# LPCB220_-_AUXPROP_INTERFACE.net
KiCad netlist of a schematic drawn in Altium Designer
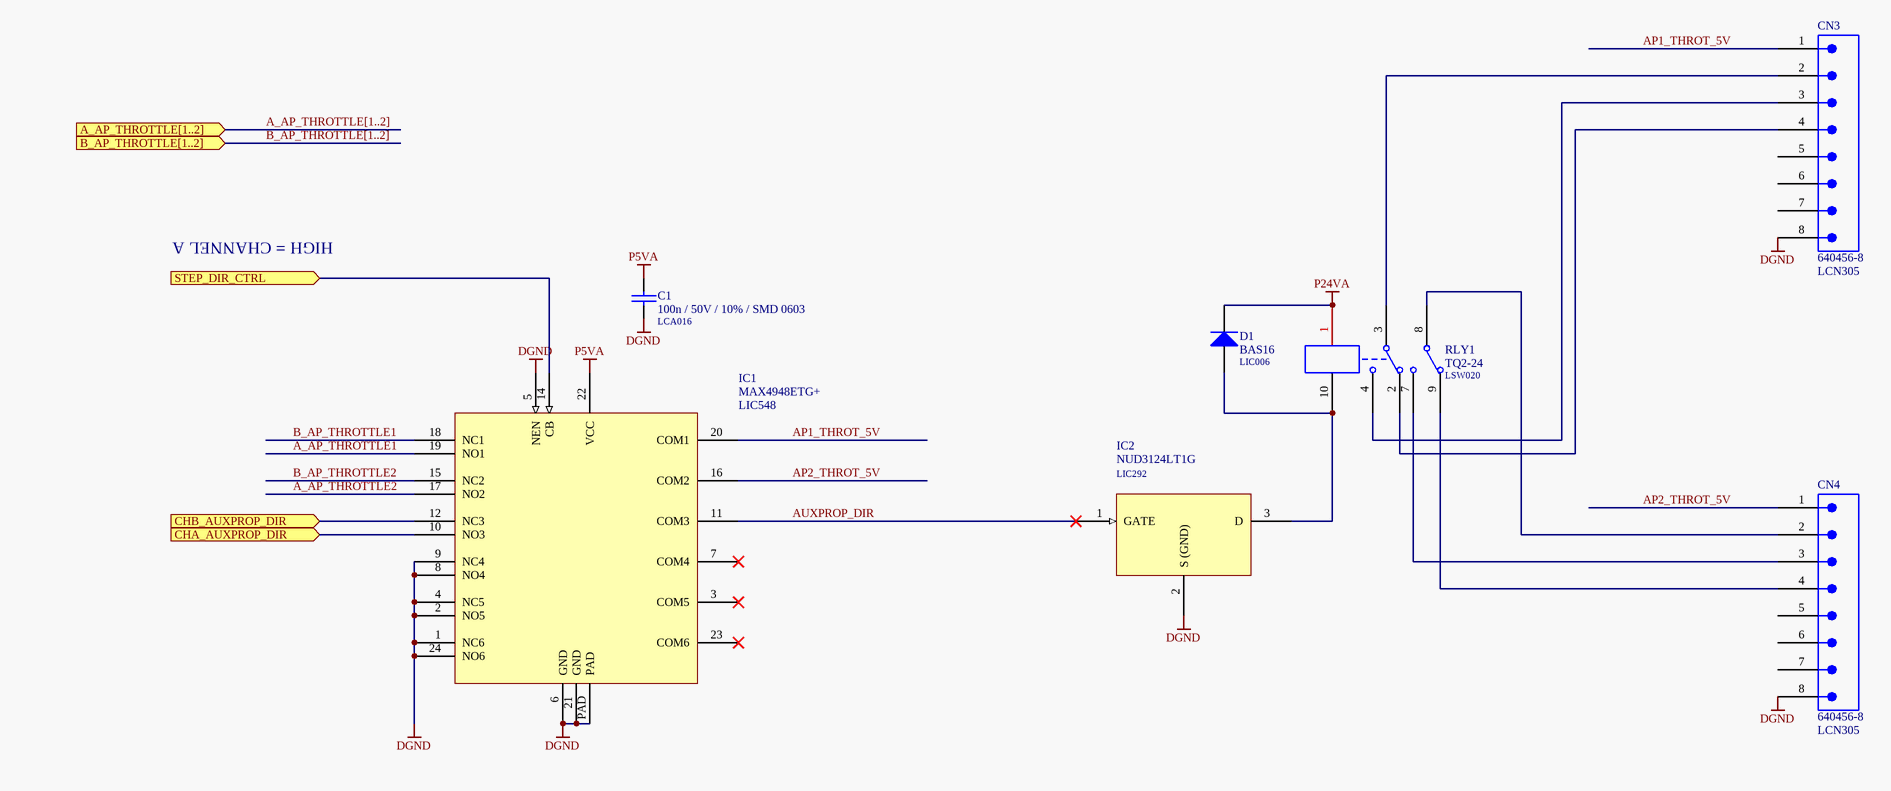
[diagram p0: LPCB220 - AUXPROP INTERFACE.SchDoc]

(export (version "E")
  (design (tool "Eeschema 10.0.6"))
  (components
    (comp (ref "C1")
      (value "100n / 50V / 10% / SMD 0603")
      (footprint "LFP011__CC1608-0603-IPC7351_B")
      (description "Capacitor, Ceramic Chip, 100nF (0.1uF), 50V, 5%, SMD 0603 [LCA016]")
      (fields (field (name "LDL_NUMBER") "LCA016"))
      (libsource (lib "LDL_Capacitors") (part "100n / 50V / 10% / SMD 0603"))
    )
    (comp (ref "CN3")
      (value "640456-8")
      (footprint "640456-8")
      (description "Connector, Male Header, 8 Way")
      (fields (field (name "LDL_NUMBER") "LCN305"))
      (libsource (lib "LDL_Connectors") (part "640456-8"))
    )
    (comp (ref "CN4")
      (value "640456-8")
      (footprint "640456-8")
      (description "Connector, Male Header, 8 Way")
      (fields (field (name "LDL_NUMBER") "LCN305"))
      (libsource (lib "LDL_Connectors") (part "640456-8"))
    )
    (comp (ref "D1")
      (value "BAS16")
      (footprint "LFP021__SOT23")
      (description "Diode, Small Signal, 0.2A, 85V, SMD SOT-23 [LIC006]")
      (fields (field (name "LDL_NUMBER") "LIC006"))
      (libsource (lib "LDL_Semiconductors") (part "BAS16"))
    )
    (comp (ref "IC1")
      (value "MAX4948ETG+")
      (footprint "LFP095__QFN127P600-8N")
      (description "IC, Analog Switch, SMD [LIC548]")
      (fields (field (name "LDL_NUMBER") "LIC548"))
      (libsource (lib "LDL_Semiconductors") (part "MAX4948ETG+"))
    )
    (comp (ref "IC2")
      (value "NUD3124LT1G")
      (footprint "LFP021__SOT23")
      (description "IC, Relay Driver, 28V Industrial, SMD SOT23 [LIC292]")
      (fields (field (name "LDL_NUMBER") "LIC292"))
      (libsource (lib "LDL_Semiconductors") (part "NUD3124LT1G"))
    )
    (comp (ref "RLY1")
      (value "TQ2-24")
      (footprint "TQ2")
      (description "Relay, DPDT, Non Latching, 24VDC Coil, 1A Rating, PTH")
      (fields (field (name "LDL_NUMBER") "LSW020"))
      (libsource (lib "LDL_Switching") (part "TQ2-24"))
    )
  )
  (nets
    (net (code "1") (name "/AP1_THROT_5V") (class "Default")
      (node (ref "CN3") (pin "1") (pinfunction "1_1") (pintype "passive"))
      (node (ref "IC1") (pin "20") (pinfunction "COM1_20") (pintype "passive"))
    )
    (net (code "2") (name "/AP2_THROT_5V") (class "Default")
      (node (ref "CN4") (pin "1") (pinfunction "1_1") (pintype "passive"))
      (node (ref "IC1") (pin "16") (pinfunction "COM2_16") (pintype "passive"))
    )
    (net (code "3") (name "/AUXPROP_DIR") (class "Default")
      (node (ref "IC1") (pin "11") (pinfunction "COM3_11") (pintype "passive"))
      (node (ref "IC2") (pin "1") (pinfunction "GATE_1") (pintype "input"))
    )
    (net (code "4") (name "/A_AP_THROTTLE1") (class "Default")
      (node (ref "IC1") (pin "19") (pinfunction "NO1_19") (pintype "passive"))
    )
    (net (code "5") (name "/A_AP_THROTTLE2") (class "Default")
      (node (ref "IC1") (pin "17") (pinfunction "NO2_17") (pintype "passive"))
    )
    (net (code "7") (name "/B_AP_THROTTLE1") (class "Default")
      (node (ref "IC1") (pin "18") (pinfunction "NC1_18") (pintype "passive"))
    )
    (net (code "8") (name "/B_AP_THROTTLE2") (class "Default")
      (node (ref "IC1") (pin "15") (pinfunction "NC2_15") (pintype "passive"))
    )
    (net (code "10") (name "/CHA_AUXPROP_DIR") (class "Default")
      (node (ref "IC1") (pin "10") (pinfunction "NO3_10") (pintype "passive"))
    )
    (net (code "11") (name "/CHB_AUXPROP_DIR") (class "Default")
      (node (ref "IC1") (pin "12") (pinfunction "NC3_12") (pintype "passive"))
    )
    (net (code "12") (name "/STEP_DIR_CTRL") (class "Default")
      (node (ref "IC1") (pin "14") (pinfunction "CB_14") (pintype "input"))
    )
    (net (code "13") (name "DGND") (class "Default")
      (node (ref "C1") (pin "2") (pintype "passive"))
      (node (ref "CN3") (pin "8") (pinfunction "8_8") (pintype "passive"))
      (node (ref "CN4") (pin "8") (pinfunction "8_8") (pintype "passive"))
      (node (ref "IC1") (pin "1") (pinfunction "NC6_1") (pintype "passive"))
      (node (ref "IC1") (pin "2") (pinfunction "NO5_2") (pintype "passive"))
      (node (ref "IC1") (pin "21") (pinfunction "GND_21") (pintype "power_in"))
      (node (ref "IC1") (pin "24") (pinfunction "NO6_24") (pintype "passive"))
      (node (ref "IC1") (pin "4") (pinfunction "NC5_4") (pintype "passive"))
      (node (ref "IC1") (pin "5") (pinfunction "NEN_5") (pintype "input"))
      (node (ref "IC1") (pin "6") (pinfunction "GND_6") (pintype "power_in"))
      (node (ref "IC1") (pin "8") (pinfunction "NO4_8") (pintype "passive"))
      (node (ref "IC1") (pin "9") (pinfunction "NC4_9") (pintype "passive"))
      (node (ref "IC1") (pin "PAD") (pinfunction "PAD_PAD") (pintype "power_in"))
      (node (ref "IC2") (pin "2") (pinfunction "S_(GND)_2") (pintype "passive"))
    )
    (net (code "14") (name "Net-(CN3-Pad2)") (class "Default")
      (node (ref "CN3") (pin "2") (pinfunction "2_2") (pintype "passive"))
      (node (ref "RLY1") (pin "3") (pinfunction "3_3") (pintype "passive"))
    )
    (net (code "15") (name "Net-(CN3-Pad3)") (class "Default")
      (node (ref "CN3") (pin "3") (pinfunction "3_3") (pintype "passive"))
      (node (ref "RLY1") (pin "4") (pinfunction "4_4") (pintype "passive"))
    )
    (net (code "16") (name "Net-(CN3-Pad4)") (class "Default")
      (node (ref "CN3") (pin "4") (pinfunction "4_4") (pintype "passive"))
      (node (ref "RLY1") (pin "2") (pinfunction "2_2") (pintype "passive"))
    )
    (net (code "17") (name "Net-(CN4-Pad2)") (class "Default")
      (node (ref "CN4") (pin "2") (pinfunction "2_2") (pintype "passive"))
      (node (ref "RLY1") (pin "8") (pinfunction "8_8") (pintype "passive"))
    )
    (net (code "18") (name "Net-(CN4-Pad3)") (class "Default")
      (node (ref "CN4") (pin "3") (pinfunction "3_3") (pintype "passive"))
      (node (ref "RLY1") (pin "7") (pinfunction "7_7") (pintype "passive"))
    )
    (net (code "19") (name "Net-(CN4-Pad4)") (class "Default")
      (node (ref "CN4") (pin "4") (pinfunction "4_4") (pintype "passive"))
      (node (ref "RLY1") (pin "9") (pinfunction "9_9") (pintype "passive"))
    )
    (net (code "20") (name "Net-(D1-A)") (class "Default")
      (node (ref "D1") (pin "1") (pinfunction "A_1") (pintype "passive"))
      (node (ref "IC2") (pin "3") (pinfunction "D_3") (pintype "passive"))
      (node (ref "RLY1") (pin "10") (pinfunction "10_10") (pintype "passive"))
    )
    (net (code "21") (name "P5VA") (class "Default")
      (node (ref "C1") (pin "1") (pintype "passive"))
      (node (ref "IC1") (pin "22") (pinfunction "VCC_22") (pintype "power_in"))
    )
    (net (code "22") (name "P24VA") (class "Default")
      (node (ref "D1") (pin "3") (pinfunction "K_3") (pintype "passive"))
      (node (ref "RLY1") (pin "1") (pinfunction "1_1") (pintype "passive"))
    )
    (net (code "23") (name "unconnected-(CN3-Pad5)") (class "Default")
      (node (ref "CN3") (pin "5") (pinfunction "5_5") (pintype "passive"))
    )
    (net (code "24") (name "unconnected-(CN3-Pad6)") (class "Default")
      (node (ref "CN3") (pin "6") (pinfunction "6_6") (pintype "passive"))
    )
    (net (code "25") (name "unconnected-(CN3-Pad7)") (class "Default")
      (node (ref "CN3") (pin "7") (pinfunction "7_7") (pintype "passive"))
    )
    (net (code "26") (name "unconnected-(CN4-Pad5)") (class "Default")
      (node (ref "CN4") (pin "5") (pinfunction "5_5") (pintype "passive"))
    )
    (net (code "27") (name "unconnected-(CN4-Pad6)") (class "Default")
      (node (ref "CN4") (pin "6") (pinfunction "6_6") (pintype "passive"))
    )
    (net (code "28") (name "unconnected-(CN4-Pad7)") (class "Default")
      (node (ref "CN4") (pin "7") (pinfunction "7_7") (pintype "passive"))
    )
    (net (code "29") (name "unconnected-(IC1-COM4-Pad7)") (class "Default")
      (node (ref "IC1") (pin "7") (pinfunction "COM4_7") (pintype "passive+no_connect"))
    )
    (net (code "30") (name "unconnected-(IC1-COM5-Pad3)") (class "Default")
      (node (ref "IC1") (pin "3") (pinfunction "COM5_3") (pintype "passive+no_connect"))
    )
    (net (code "31") (name "unconnected-(IC1-COM6-Pad23)") (class "Default")
      (node (ref "IC1") (pin "23") (pinfunction "COM6_23") (pintype "passive+no_connect"))
    )
  )
)
